# LEDRelay150.net
KiCad netlist of a schematic drawn in Altium Designer
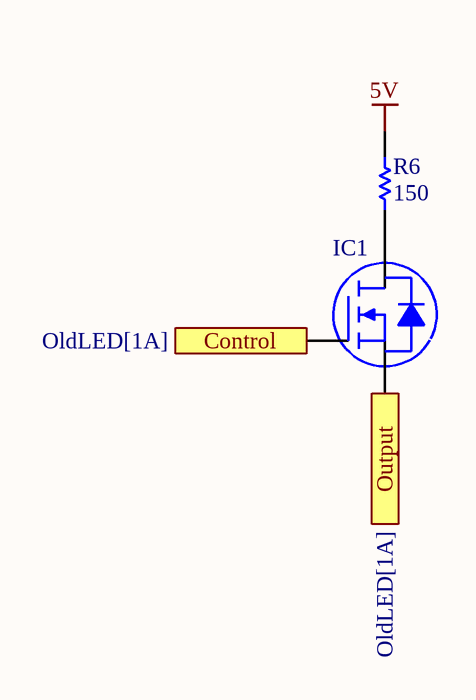
[diagram p0: LEDRelay150.SchDoc]

(export (version "E")
  (design (tool "Eeschema 10.0.6"))
  (components
    (comp (ref "IC1")
      (value "DMN3023L-7")
      (footprint "DIODES SOT-23-3")
      (description "MOSFET N-CH 30V 6.2A SOT23")
      (fields (field (name "MANUFACTURER") "Diodes Incorporated"))
      (libsource (lib "IIT Motorsports") (part "DIODES INC MOSFET N-CH SOT-23-3"))
    )
    (comp (ref "R6")
      (value "150")
      (footprint "RESC2013X70X40NL20T20")
      (description "RES SMD 150 OHM 1% 1/8W 0805")
      (fields (field (name "TOLERANCE") "1%") (field (name "Comment") "ERJ-6ENF1500V"))
      (libsource (lib "IIT Motorsports") (part "RES"))
    )
  )
  (nets
    (net (code "1") (name "/Control") (class "Default")
      (node (ref "IC1") (pin "1") (pinfunction "G_1") (pintype "passive"))
    )
    (net (code "2") (name "/Output") (class "Default")
      (node (ref "IC1") (pin "2") (pinfunction "S_2") (pintype "passive"))
    )
    (net (code "3") (name "5V") (class "Default")
      (node (ref "R6") (pin "2") (pinfunction "2_2") (pintype "passive"))
    )
    (net (code "4") (name "Net-(IC1-D)") (class "Default")
      (node (ref "IC1") (pin "3") (pinfunction "D_3") (pintype "passive"))
      (node (ref "R6") (pin "1") (pinfunction "1_1") (pintype "passive"))
    )
  )
)
